# ASD2121.net
KiCad netlist of a schematic drawn in EAGLE
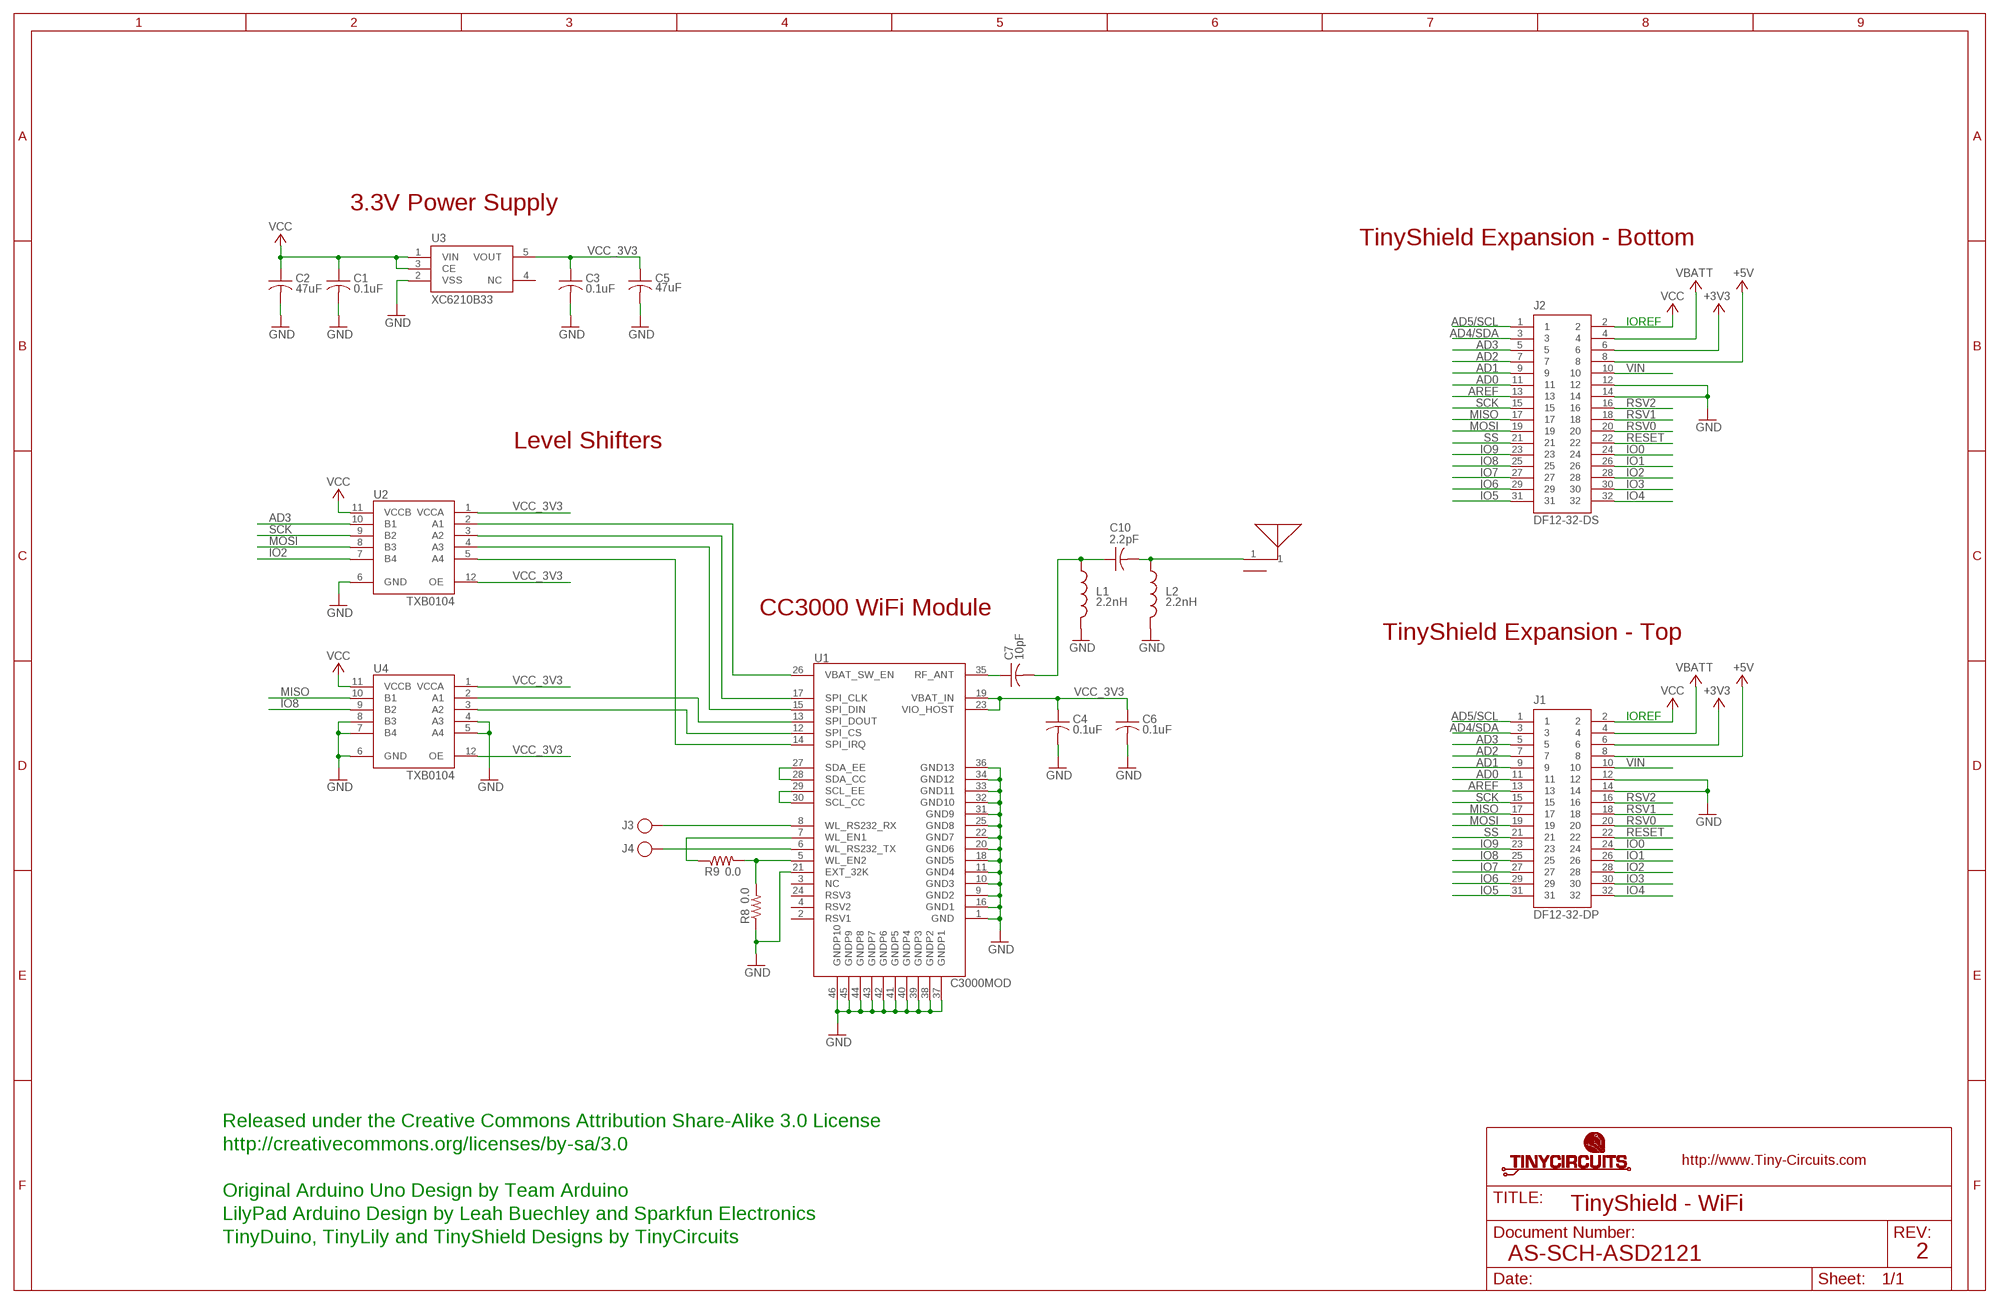
[diagram p0: schematic, sheet 1]

(export (version "E")
  (design (tool "Eeschema 10.0.6"))
  (components
    (comp (ref "ANT1")
      (value "AS-ITM-00082")
      (footprint "eagle-import:2G4_ANT")
      (libsource (lib "eagle-import") (part "AS-ITM-00082"))
    )
    (comp (ref "C1")
      (value "0.1uF")
      (footprint "eagle-import:C0402")
      (fields (field (name "PARTNO") "AS-ITM-00008") (field (name "PARTNO_1") "AS-ITM-00008"))
      (libsource (lib "eagle-import") (part "AS-ITM-00008"))
    )
    (comp (ref "C2")
      (value "47uF")
      (footprint "eagle-import:C1206")
      (fields (field (name "PARTNUM") "AS-ITM-00049") (field (name "PARTNUM_1") "AS-ITM-00049"))
      (libsource (lib "eagle-import") (part "AS-ITM-00049"))
    )
    (comp (ref "C3")
      (value "0.1uF")
      (footprint "eagle-import:C0402")
      (fields (field (name "PARTNO") "AS-ITM-00008") (field (name "PARTNO_1") "AS-ITM-00008"))
      (libsource (lib "eagle-import") (part "AS-ITM-00008"))
    )
    (comp (ref "C4")
      (value "0.1uF")
      (footprint "eagle-import:C0402")
      (fields (field (name "PARTNO") "AS-ITM-00008") (field (name "PARTNO_1") "AS-ITM-00008"))
      (libsource (lib "eagle-import") (part "AS-ITM-00008"))
    )
    (comp (ref "C5")
      (value "47uF")
      (footprint "eagle-import:C1206")
      (fields (field (name "PARTNUM") "AS-ITM-00049"))
      (libsource (lib "eagle-import") (part "AS-ITM-00049"))
    )
    (comp (ref "C6")
      (value "0.1uF")
      (footprint "eagle-import:C0402")
      (fields (field (name "PARTNO") "AS-ITM-00008") (field (name "PARTNO_1") "AS-ITM-00008"))
      (libsource (lib "eagle-import") (part "AS-ITM-00008"))
    )
    (comp (ref "C7")
      (value "10pF")
      (footprint "eagle-import:C0402")
      (fields (field (name "PARTNO") "AS-ITM-00107") (field (name "PARTNO_1") "AS-ITM-00107"))
      (libsource (lib "eagle-import") (part "AS-ITM-00107"))
    )
    (comp (ref "C10")
      (value "2.2pF")
      (footprint "eagle-import:C0402")
      (fields (field (name "PARTNO") "AS-ITM-00106") (field (name "PARTNO_1") "AS-ITM-00106"))
      (libsource (lib "eagle-import") (part "AS-ITM-00106"))
    )
    (comp (ref "J1")
      (value "DF12-32-DP")
      (footprint "eagle-import:DF12-32-DP")
      (fields (field (name "PARTNO") "AS-ITM-00015") (field (name "PARTNO_1") "AS-ITM-00015"))
      (libsource (lib "eagle-import") (part "AS-ITM-00015"))
    )
    (comp (ref "J2")
      (value "DF12-32-DS")
      (footprint "eagle-import:DF12-32-DS")
      (fields (field (name "PARTNO") "AS-ITM-00012") (field (name "PARTNO_1") "AS-ITM-00012"))
      (libsource (lib "eagle-import") (part "AS-ITM-00012"))
    )
    (comp (ref "J3")
      (value "PIN_1X.1\"SQ_PAD")
      (footprint "eagle-import:TEST_POINT")
      (libsource (lib "eagle-import") (part "PIN_1X.1{dblquote}SQ_PAD"))
    )
    (comp (ref "J4")
      (value "PIN_1X.1\"SQ_PAD")
      (footprint "eagle-import:TEST_POINT")
      (libsource (lib "eagle-import") (part "PIN_1X.1{dblquote}SQ_PAD"))
    )
    (comp (ref "L1")
      (value "2.2nH")
      (footprint "eagle-import:C0402")
      (fields (field (name "PARTNO") "AS-ITM-00108") (field (name "PARTNO_1") "AS-ITM-00108"))
      (libsource (lib "eagle-import") (part "AS-ITM-00108"))
    )
    (comp (ref "L2")
      (value "2.2nH")
      (footprint "eagle-import:C0402")
      (fields (field (name "PARTNO") "AS-ITM-00108") (field (name "PARTNO_1") "AS-ITM-00108"))
      (libsource (lib "eagle-import") (part "AS-ITM-00108"))
    )
    (comp (ref "R8")
      (value "0.0")
      (footprint "eagle-import:0402")
      (fields (field (name "PARTNO") "AS-ITM-00076"))
      (libsource (lib "eagle-import") (part "AS-ITM-00076"))
    )
    (comp (ref "R9")
      (value "0.0")
      (footprint "eagle-import:0402_SHORT")
      (libsource (lib "eagle-import") (part "AS-ITM-000760402_SHORT"))
    )
    (comp (ref "U1")
      (value "C3000MOD")
      (footprint "eagle-import:CC3000MOD")
      (fields (field (name "PARTNO") "AS_ITM-00079"))
      (libsource (lib "eagle-import") (part "AS-ITM-00079"))
    )
    (comp (ref "U2")
      (value "TXB0104")
      (footprint "eagle-import:UQFN-12")
      (fields (field (name "PARTNO") "AS-ITM-00048"))
      (libsource (lib "eagle-import") (part "AS-ITM-00048"))
    )
    (comp (ref "U3")
      (value "XC6210B33")
      (footprint "eagle-import:SOT-25")
      (fields (field (name "PARTNO") "AS-ITM-00046"))
      (libsource (lib "eagle-import") (part "AS-ITM-00046"))
    )
    (comp (ref "U4")
      (value "TXB0104")
      (footprint "eagle-import:UQFN-12")
      (fields (field (name "PARTNO") "AS-ITM-00048"))
      (libsource (lib "eagle-import") (part "AS-ITM-00048"))
    )
  )
  (nets
    (net (code "1") (name "+3V3") (class "Default")
      (node (ref "J1") (pin "6") (pinfunction "6_6") (pintype "bidirectional"))
      (node (ref "J2") (pin "6") (pinfunction "6_6") (pintype "bidirectional"))
    )
    (net (code "2") (name "+5V") (class "Default")
      (node (ref "J1") (pin "8") (pinfunction "8_8") (pintype "bidirectional"))
      (node (ref "J2") (pin "8") (pinfunction "8_8") (pintype "bidirectional"))
    )
    (net (code "3") (name "/AD0") (class "Default")
      (node (ref "J1") (pin "11") (pinfunction "11_11") (pintype "bidirectional"))
      (node (ref "J2") (pin "11") (pinfunction "11_11") (pintype "bidirectional"))
    )
    (net (code "4") (name "/AD1") (class "Default")
      (node (ref "J1") (pin "9") (pinfunction "9_9") (pintype "bidirectional"))
      (node (ref "J2") (pin "9") (pinfunction "9_9") (pintype "bidirectional"))
    )
    (net (code "5") (name "/AD2") (class "Default")
      (node (ref "J1") (pin "7") (pinfunction "7_7") (pintype "bidirectional"))
      (node (ref "J2") (pin "7") (pinfunction "7_7") (pintype "bidirectional"))
    )
    (net (code "6") (name "/AD3") (class "Default")
      (node (ref "J1") (pin "5") (pinfunction "5_5") (pintype "bidirectional"))
      (node (ref "J2") (pin "5") (pinfunction "5_5") (pintype "bidirectional"))
      (node (ref "U2") (pin "10") (pinfunction "B1_10") (pintype "bidirectional"))
    )
    (net (code "7") (name "/AD4{slash}SDA") (class "Default")
      (node (ref "J1") (pin "3") (pinfunction "3_3") (pintype "bidirectional"))
      (node (ref "J2") (pin "3") (pinfunction "3_3") (pintype "bidirectional"))
    )
    (net (code "8") (name "/AD5{slash}SCL") (class "Default")
      (node (ref "J1") (pin "1") (pinfunction "1_1") (pintype "bidirectional"))
      (node (ref "J2") (pin "1") (pinfunction "1_1") (pintype "bidirectional"))
    )
    (net (code "9") (name "/AREF") (class "Default")
      (node (ref "J1") (pin "13") (pinfunction "13_13") (pintype "bidirectional"))
      (node (ref "J2") (pin "13") (pinfunction "13_13") (pintype "bidirectional"))
    )
    (net (code "10") (name "/IO0") (class "Default")
      (node (ref "J1") (pin "24") (pinfunction "24_24") (pintype "bidirectional"))
      (node (ref "J2") (pin "24") (pinfunction "24_24") (pintype "bidirectional"))
    )
    (net (code "11") (name "/IO1") (class "Default")
      (node (ref "J1") (pin "26") (pinfunction "26_26") (pintype "bidirectional"))
      (node (ref "J2") (pin "26") (pinfunction "26_26") (pintype "bidirectional"))
    )
    (net (code "12") (name "/IO2") (class "Default")
      (node (ref "J1") (pin "28") (pinfunction "28_28") (pintype "bidirectional"))
      (node (ref "J2") (pin "28") (pinfunction "28_28") (pintype "bidirectional"))
      (node (ref "U2") (pin "7") (pinfunction "B4_7") (pintype "bidirectional"))
    )
    (net (code "13") (name "/IO3") (class "Default")
      (node (ref "J1") (pin "30") (pinfunction "30_30") (pintype "bidirectional"))
      (node (ref "J2") (pin "30") (pinfunction "30_30") (pintype "bidirectional"))
    )
    (net (code "14") (name "/IO4") (class "Default")
      (node (ref "J1") (pin "32") (pinfunction "32_32") (pintype "bidirectional"))
      (node (ref "J2") (pin "32") (pinfunction "32_32") (pintype "bidirectional"))
    )
    (net (code "15") (name "/IO5") (class "Default")
      (node (ref "J1") (pin "31") (pinfunction "31_31") (pintype "bidirectional"))
      (node (ref "J2") (pin "31") (pinfunction "31_31") (pintype "bidirectional"))
    )
    (net (code "16") (name "/IO6") (class "Default")
      (node (ref "J1") (pin "29") (pinfunction "29_29") (pintype "bidirectional"))
      (node (ref "J2") (pin "29") (pinfunction "29_29") (pintype "bidirectional"))
    )
    (net (code "17") (name "/IO7") (class "Default")
      (node (ref "J1") (pin "27") (pinfunction "27_27") (pintype "bidirectional"))
      (node (ref "J2") (pin "27") (pinfunction "27_27") (pintype "bidirectional"))
    )
    (net (code "18") (name "/IO8") (class "Default")
      (node (ref "J1") (pin "25") (pinfunction "25_25") (pintype "bidirectional"))
      (node (ref "J2") (pin "25") (pinfunction "25_25") (pintype "bidirectional"))
      (node (ref "U4") (pin "9") (pinfunction "B2_9") (pintype "bidirectional"))
    )
    (net (code "19") (name "/IO9") (class "Default")
      (node (ref "J1") (pin "23") (pinfunction "23_23") (pintype "bidirectional"))
      (node (ref "J2") (pin "23") (pinfunction "23_23") (pintype "bidirectional"))
    )
    (net (code "20") (name "/MISO") (class "Default")
      (node (ref "J1") (pin "17") (pinfunction "17_17") (pintype "bidirectional"))
      (node (ref "J2") (pin "17") (pinfunction "17_17") (pintype "bidirectional"))
      (node (ref "U4") (pin "10") (pinfunction "B1_10") (pintype "bidirectional"))
    )
    (net (code "21") (name "/MOSI") (class "Default")
      (node (ref "J1") (pin "19") (pinfunction "19_19") (pintype "bidirectional"))
      (node (ref "J2") (pin "19") (pinfunction "19_19") (pintype "bidirectional"))
      (node (ref "U2") (pin "8") (pinfunction "B3_8") (pintype "bidirectional"))
    )
    (net (code "22") (name "/RESET") (class "Default")
      (node (ref "J1") (pin "22") (pinfunction "22_22") (pintype "bidirectional"))
      (node (ref "J2") (pin "22") (pinfunction "22_22") (pintype "bidirectional"))
    )
    (net (code "23") (name "/RSV0") (class "Default")
      (node (ref "J1") (pin "20") (pinfunction "20_20") (pintype "bidirectional"))
      (node (ref "J2") (pin "20") (pinfunction "20_20") (pintype "bidirectional"))
    )
    (net (code "24") (name "/RSV1") (class "Default")
      (node (ref "J1") (pin "18") (pinfunction "18_18") (pintype "bidirectional"))
      (node (ref "J2") (pin "18") (pinfunction "18_18") (pintype "bidirectional"))
    )
    (net (code "25") (name "/RSV2") (class "Default")
      (node (ref "J1") (pin "16") (pinfunction "16_16") (pintype "bidirectional"))
      (node (ref "J2") (pin "16") (pinfunction "16_16") (pintype "bidirectional"))
    )
    (net (code "26") (name "/SCK") (class "Default")
      (node (ref "J1") (pin "15") (pinfunction "15_15") (pintype "bidirectional"))
      (node (ref "J2") (pin "15") (pinfunction "15_15") (pintype "bidirectional"))
      (node (ref "U2") (pin "9") (pinfunction "B2_9") (pintype "bidirectional"))
    )
    (net (code "27") (name "/SS") (class "Default")
      (node (ref "J1") (pin "21") (pinfunction "21_21") (pintype "bidirectional"))
      (node (ref "J2") (pin "21") (pinfunction "21_21") (pintype "bidirectional"))
    )
    (net (code "28") (name "/VCC_3V3") (class "Default")
      (node (ref "C3") (pin "1") (pinfunction "1_1") (pintype "passive"))
      (node (ref "C4") (pin "1") (pinfunction "1_1") (pintype "passive"))
      (node (ref "C5") (pin "1") (pinfunction "1_1") (pintype "passive"))
      (node (ref "C6") (pin "1") (pinfunction "1_1") (pintype "passive"))
      (node (ref "U1") (pin "19") (pinfunction "VBAT_IN_19") (pintype "bidirectional"))
      (node (ref "U1") (pin "23") (pinfunction "VIO_HOST_23") (pintype "bidirectional"))
      (node (ref "U2") (pin "1") (pinfunction "VCCA_1") (pintype "bidirectional"))
      (node (ref "U2") (pin "12") (pinfunction "OE_12") (pintype "bidirectional"))
      (node (ref "U3") (pin "5") (pinfunction "VOUT_5") (pintype "bidirectional"))
      (node (ref "U4") (pin "1") (pinfunction "VCCA_1") (pintype "bidirectional"))
      (node (ref "U4") (pin "12") (pinfunction "OE_12") (pintype "bidirectional"))
    )
    (net (code "29") (name "/VIN") (class "Default")
      (node (ref "J1") (pin "10") (pinfunction "10_10") (pintype "bidirectional"))
      (node (ref "J2") (pin "10") (pinfunction "10_10") (pintype "bidirectional"))
    )
    (net (code "30") (name "GND") (class "Default")
      (node (ref "C1") (pin "2") (pinfunction "2_2") (pintype "passive"))
      (node (ref "C2") (pin "2") (pinfunction "2_2") (pintype "passive"))
      (node (ref "C3") (pin "2") (pinfunction "2_2") (pintype "passive"))
      (node (ref "C4") (pin "2") (pinfunction "2_2") (pintype "passive"))
      (node (ref "C5") (pin "2") (pinfunction "2_2") (pintype "passive"))
      (node (ref "C6") (pin "2") (pinfunction "2_2") (pintype "passive"))
      (node (ref "J1") (pin "12") (pinfunction "12_12") (pintype "bidirectional"))
      (node (ref "J1") (pin "14") (pinfunction "14_14") (pintype "bidirectional"))
      (node (ref "J2") (pin "12") (pinfunction "12_12") (pintype "bidirectional"))
      (node (ref "J2") (pin "14") (pinfunction "14_14") (pintype "bidirectional"))
      (node (ref "L1") (pin "2") (pinfunction "2_2") (pintype "passive"))
      (node (ref "L2") (pin "2") (pinfunction "2_2") (pintype "passive"))
      (node (ref "R8") (pin "1") (pinfunction "1_1") (pintype "passive"))
      (node (ref "U1") (pin "1") (pinfunction "GND_1") (pintype "bidirectional"))
      (node (ref "U1") (pin "10") (pinfunction "GND3_10") (pintype "bidirectional"))
      (node (ref "U1") (pin "11") (pinfunction "GND4_11") (pintype "bidirectional"))
      (node (ref "U1") (pin "16") (pinfunction "GND1_16") (pintype "bidirectional"))
      (node (ref "U1") (pin "18") (pinfunction "GND5_18") (pintype "bidirectional"))
      (node (ref "U1") (pin "20") (pinfunction "GND6_20") (pintype "bidirectional"))
      (node (ref "U1") (pin "21") (pinfunction "EXT_32K_21") (pintype "bidirectional"))
      (node (ref "U1") (pin "22") (pinfunction "GND7_22") (pintype "bidirectional"))
      (node (ref "U1") (pin "25") (pinfunction "GND8_25") (pintype "bidirectional"))
      (node (ref "U1") (pin "31") (pinfunction "GND9_31") (pintype "bidirectional"))
      (node (ref "U1") (pin "32") (pinfunction "GND10_32") (pintype "bidirectional"))
      (node (ref "U1") (pin "33") (pinfunction "GND11_33") (pintype "bidirectional"))
      (node (ref "U1") (pin "34") (pinfunction "GND12_34") (pintype "bidirectional"))
      (node (ref "U1") (pin "36") (pinfunction "GND13_36") (pintype "bidirectional"))
      (node (ref "U1") (pin "37") (pinfunction "GNDP1_37") (pintype "bidirectional"))
      (node (ref "U1") (pin "38") (pinfunction "GNDP2_38") (pintype "bidirectional"))
      (node (ref "U1") (pin "39") (pinfunction "GNDP3_39") (pintype "bidirectional"))
      (node (ref "U1") (pin "40") (pinfunction "GNDP4_40") (pintype "bidirectional"))
      (node (ref "U1") (pin "41") (pinfunction "GNDP5_41") (pintype "bidirectional"))
      (node (ref "U1") (pin "42") (pinfunction "GNDP6_42") (pintype "bidirectional"))
      (node (ref "U1") (pin "43") (pinfunction "GNDP7_43") (pintype "bidirectional"))
      (node (ref "U1") (pin "44") (pinfunction "GNDP8_44") (pintype "bidirectional"))
      (node (ref "U1") (pin "45") (pinfunction "GNDP9_45") (pintype "bidirectional"))
      (node (ref "U1") (pin "46") (pinfunction "GNDP10_46") (pintype "bidirectional"))
      (node (ref "U1") (pin "9") (pinfunction "GND2_9") (pintype "bidirectional"))
      (node (ref "U2") (pin "6") (pinfunction "GND_6") (pintype "bidirectional"))
      (node (ref "U3") (pin "2") (pinfunction "VSS_2") (pintype "power_in"))
      (node (ref "U4") (pin "4") (pinfunction "A3_4") (pintype "bidirectional"))
      (node (ref "U4") (pin "5") (pinfunction "A4_5") (pintype "bidirectional"))
      (node (ref "U4") (pin "6") (pinfunction "GND_6") (pintype "bidirectional"))
      (node (ref "U4") (pin "7") (pinfunction "B4_7") (pintype "bidirectional"))
      (node (ref "U4") (pin "8") (pinfunction "B3_8") (pintype "bidirectional"))
    )
    (net (code "31") (name "Net-(ANT1-Pad1)") (class "Default")
      (node (ref "ANT1") (pin "1") (pinfunction "1_1") (pintype "bidirectional"))
      (node (ref "C10") (pin "2") (pinfunction "2_2") (pintype "passive"))
      (node (ref "L2") (pin "1") (pinfunction "1_1") (pintype "passive"))
    )
    (net (code "32") (name "Net-(C10-Pad1)") (class "Default")
      (node (ref "C10") (pin "1") (pinfunction "1_1") (pintype "passive"))
      (node (ref "C7") (pin "2") (pinfunction "2_2") (pintype "passive"))
      (node (ref "L1") (pin "1") (pinfunction "1_1") (pintype "passive"))
    )
    (net (code "33") (name "Net-(J3-1)") (class "Default")
      (node (ref "J3") (pin "P$1") (pinfunction "1_P$1") (pintype "bidirectional"))
      (node (ref "U1") (pin "8") (pinfunction "WL_RS232_RX_8") (pintype "bidirectional"))
    )
    (net (code "34") (name "Net-(J4-1)") (class "Default")
      (node (ref "J4") (pin "P$1") (pinfunction "1_P$1") (pintype "bidirectional"))
      (node (ref "U1") (pin "6") (pinfunction "WL_RS232_TX_6") (pintype "bidirectional"))
    )
    (net (code "35") (name "Net-(U1-RF_ANT)") (class "Default")
      (node (ref "C7") (pin "1") (pinfunction "1_1") (pintype "passive"))
      (node (ref "U1") (pin "35") (pinfunction "RF_ANT_35") (pintype "bidirectional"))
    )
    (net (code "36") (name "Net-(U1-SCL_CC)") (class "Default")
      (node (ref "U1") (pin "29") (pinfunction "SCL_EE_29") (pintype "bidirectional"))
      (node (ref "U1") (pin "30") (pinfunction "SCL_CC_30") (pintype "bidirectional"))
    )
    (net (code "37") (name "Net-(U1-SDA_CC)") (class "Default")
      (node (ref "U1") (pin "27") (pinfunction "SDA_EE_27") (pintype "bidirectional"))
      (node (ref "U1") (pin "28") (pinfunction "SDA_CC_28") (pintype "bidirectional"))
    )
    (net (code "38") (name "Net-(U1-SPI_CLK)") (class "Default")
      (node (ref "U1") (pin "17") (pinfunction "SPI_CLK_17") (pintype "bidirectional"))
      (node (ref "U2") (pin "3") (pinfunction "A2_3") (pintype "bidirectional"))
    )
    (net (code "39") (name "Net-(U1-SPI_CS)") (class "Default")
      (node (ref "U1") (pin "12") (pinfunction "SPI_CS_12") (pintype "bidirectional"))
      (node (ref "U4") (pin "3") (pinfunction "A2_3") (pintype "bidirectional"))
    )
    (net (code "40") (name "Net-(U1-SPI_DIN)") (class "Default")
      (node (ref "U1") (pin "15") (pinfunction "SPI_DIN_15") (pintype "bidirectional"))
      (node (ref "U2") (pin "4") (pinfunction "A3_4") (pintype "bidirectional"))
    )
    (net (code "41") (name "Net-(U1-SPI_DOUT)") (class "Default")
      (node (ref "U1") (pin "13") (pinfunction "SPI_DOUT_13") (pintype "bidirectional"))
      (node (ref "U4") (pin "2") (pinfunction "A1_2") (pintype "bidirectional"))
    )
    (net (code "42") (name "Net-(U1-SPI_IRQ)") (class "Default")
      (node (ref "U1") (pin "14") (pinfunction "SPI_IRQ_14") (pintype "bidirectional"))
      (node (ref "U2") (pin "5") (pinfunction "A4_5") (pintype "bidirectional"))
    )
    (net (code "43") (name "Net-(U1-VBAT_SW_EN)") (class "Default")
      (node (ref "U1") (pin "26") (pinfunction "VBAT_SW_EN_26") (pintype "bidirectional"))
      (node (ref "U2") (pin "2") (pinfunction "A1_2") (pintype "bidirectional"))
    )
    (net (code "44") (name "Net-(U1-WL_EN1)") (class "Default")
      (node (ref "R9") (pin "1") (pinfunction "1_1") (pintype "passive"))
      (node (ref "U1") (pin "7") (pinfunction "WL_EN1_7") (pintype "bidirectional"))
    )
    (net (code "45") (name "Net-(U1-WL_EN2)") (class "Default")
      (node (ref "R8") (pin "2") (pinfunction "2_2") (pintype "passive"))
      (node (ref "R9") (pin "2") (pinfunction "2_2") (pintype "passive"))
      (node (ref "U1") (pin "5") (pinfunction "WL_EN2_5") (pintype "bidirectional"))
    )
    (net (code "46") (name "VBATT") (class "Default")
      (node (ref "J1") (pin "4") (pinfunction "4_4") (pintype "bidirectional"))
      (node (ref "J2") (pin "4") (pinfunction "4_4") (pintype "bidirectional"))
    )
    (net (code "47") (name "VCC") (class "Default")
      (node (ref "C1") (pin "1") (pinfunction "1_1") (pintype "passive"))
      (node (ref "C2") (pin "1") (pinfunction "1_1") (pintype "passive"))
      (node (ref "J1") (pin "2") (pinfunction "2_2") (pintype "bidirectional"))
      (node (ref "J2") (pin "2") (pinfunction "2_2") (pintype "bidirectional"))
      (node (ref "U2") (pin "11") (pinfunction "VCCB_11") (pintype "bidirectional"))
      (node (ref "U3") (pin "1") (pinfunction "VIN_1") (pintype "bidirectional"))
      (node (ref "U3") (pin "3") (pinfunction "CE_3") (pintype "bidirectional"))
      (node (ref "U4") (pin "11") (pinfunction "VCCB_11") (pintype "bidirectional"))
    )
    (net (code "48") (name "unconnected-(ANT1-Pad2)") (class "Default")
      (node (ref "ANT1") (pin "2") (pinfunction "2_2") (pintype "bidirectional"))
    )
    (net (code "49") (name "unconnected-(U1-NC-Pad3)") (class "Default")
      (node (ref "U1") (pin "3") (pinfunction "NC_3") (pintype "bidirectional"))
    )
    (net (code "50") (name "unconnected-(U1-RSV1-Pad2)") (class "Default")
      (node (ref "U1") (pin "2") (pinfunction "RSV1_2") (pintype "bidirectional"))
    )
    (net (code "51") (name "unconnected-(U1-RSV2-Pad4)") (class "Default")
      (node (ref "U1") (pin "4") (pinfunction "RSV2_4") (pintype "bidirectional"))
    )
    (net (code "52") (name "unconnected-(U1-RSV3-Pad24)") (class "Default")
      (node (ref "U1") (pin "24") (pinfunction "RSV3_24") (pintype "bidirectional"))
    )
    (net (code "53") (name "unconnected-(U3-NC-Pad4)") (class "Default")
      (node (ref "U3") (pin "4") (pinfunction "NC_4") (pintype "bidirectional"))
    )
  )
)
